# ProPrj___2024-08-30.net
KiCad netlist of a schematic drawn in EasyEDA Pro
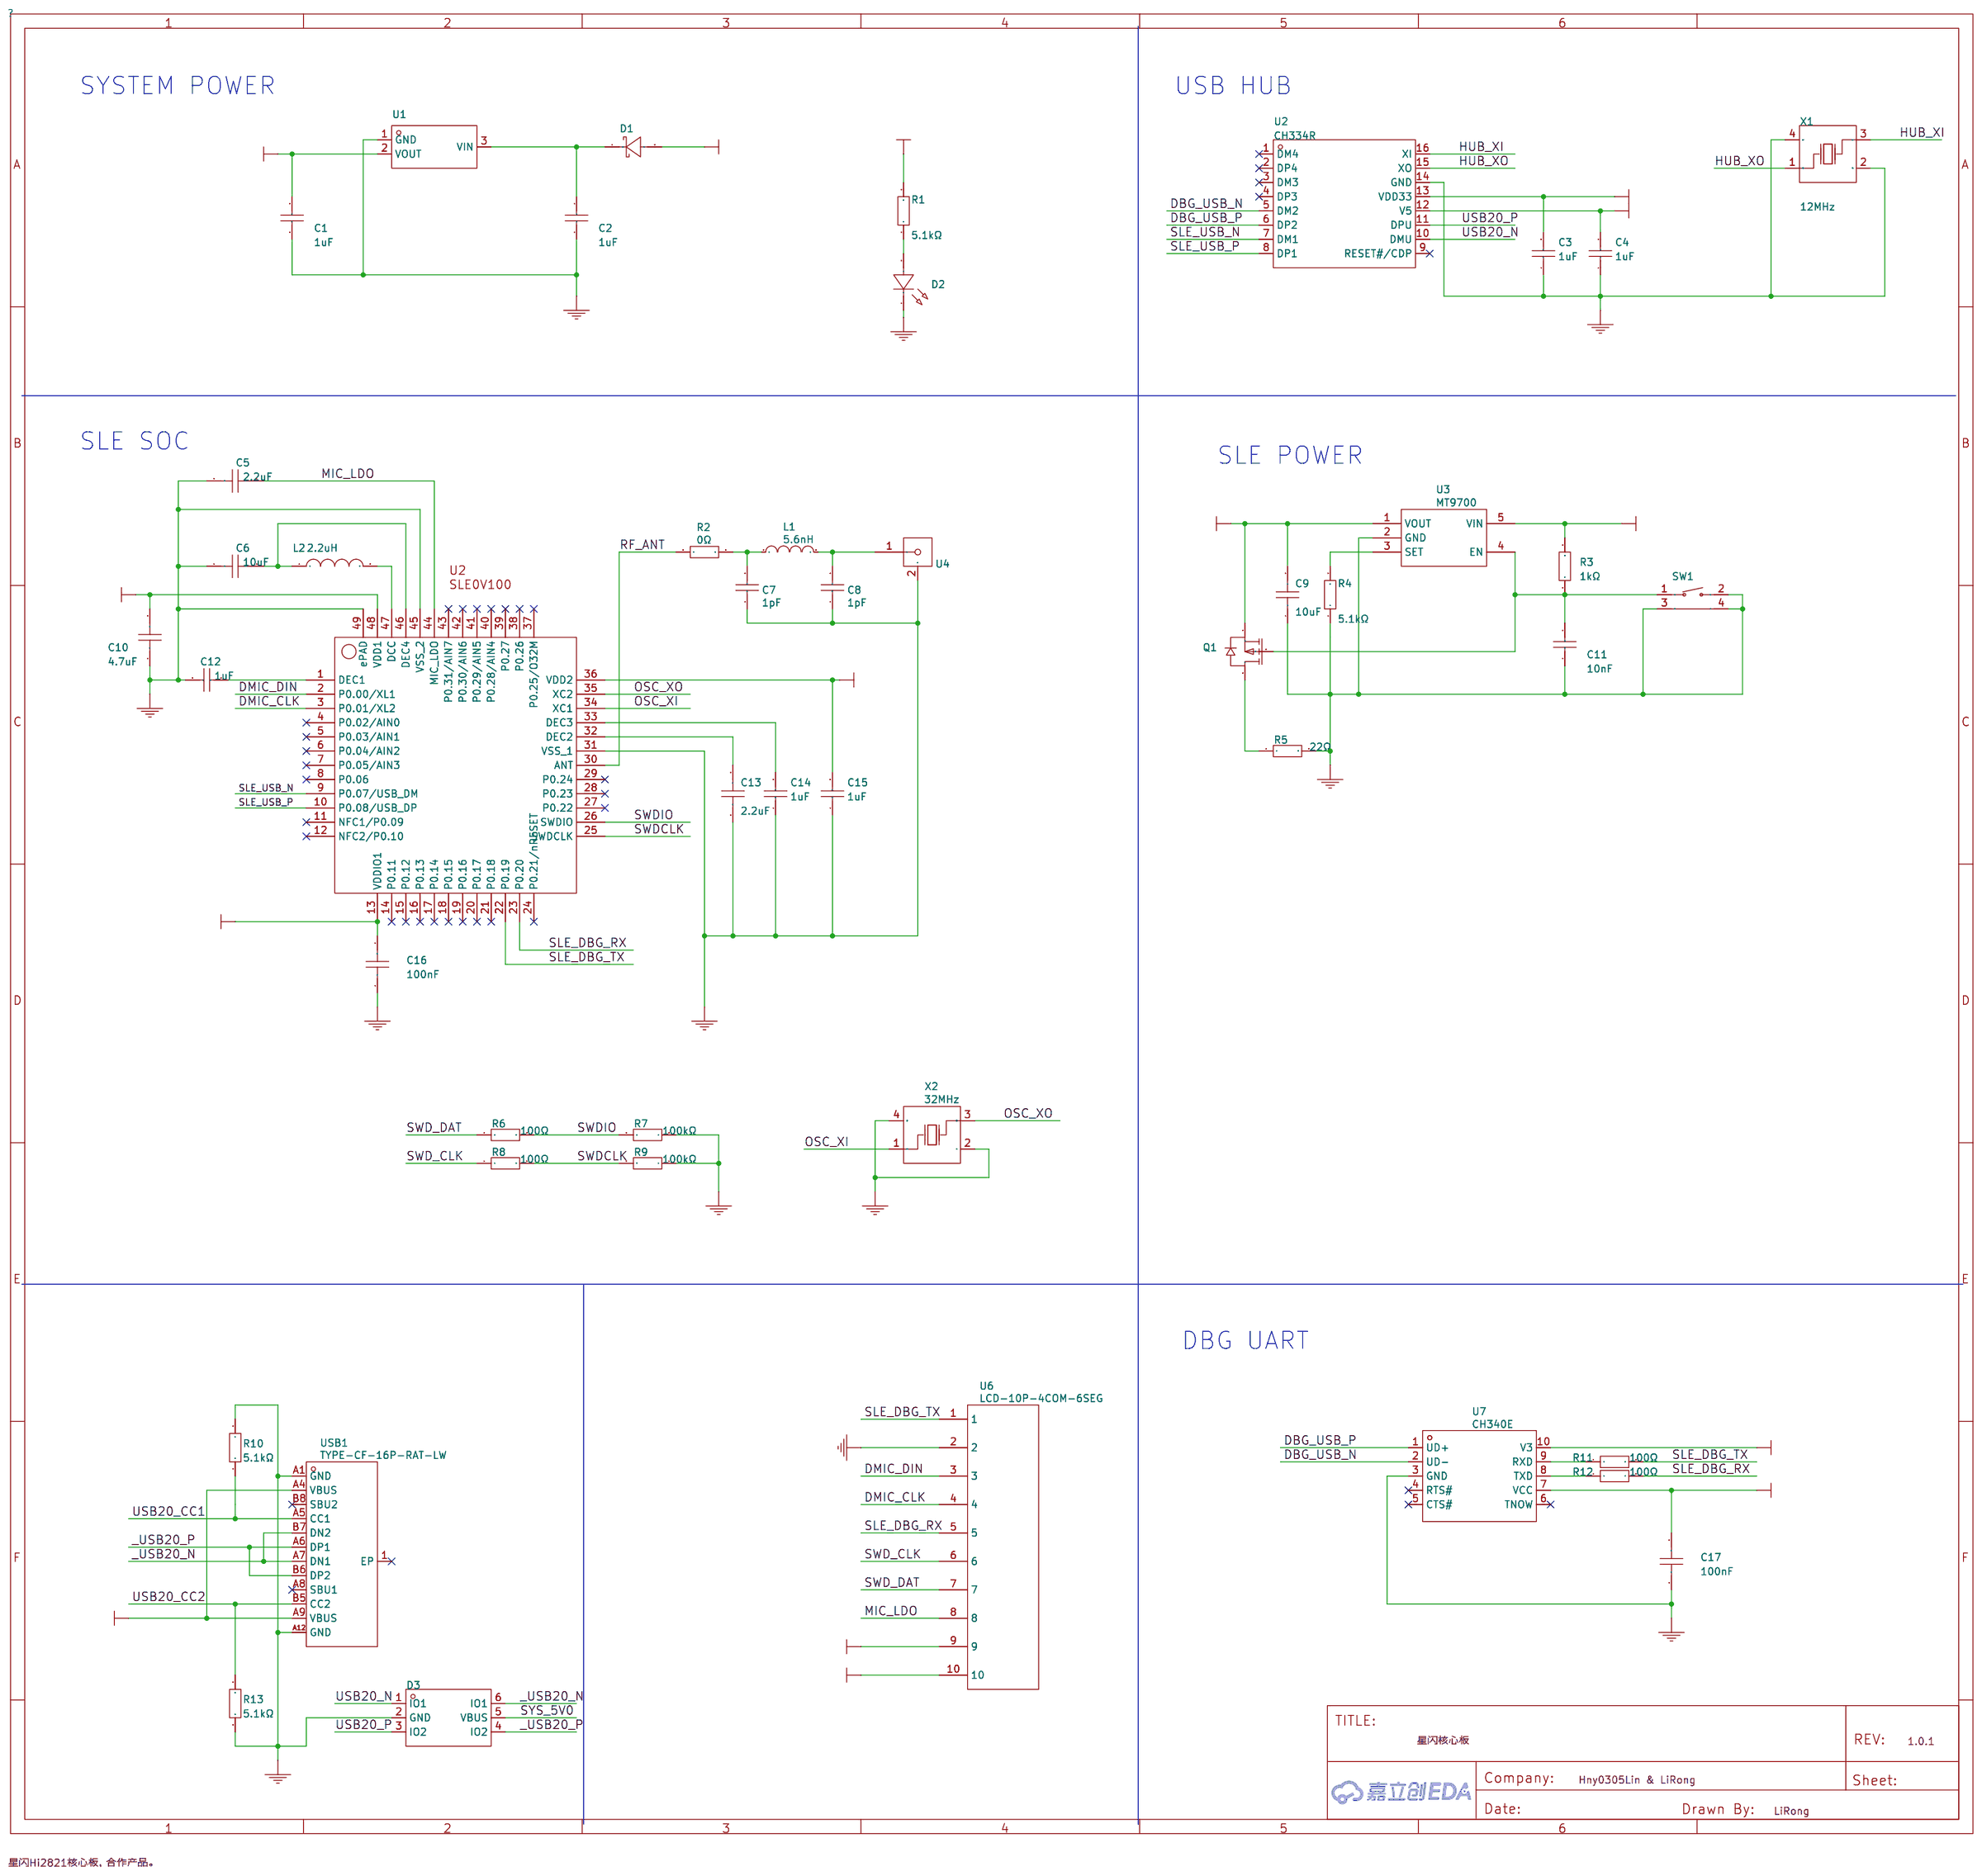
[diagram p0: schematic sheet]

(export (version "E")
  (design (tool "Eeschema 10.0.6"))
  (components
    (comp (ref "C1")
      (value "1uF")
      (footprint "easyedapro:C0603")
      (description "容值:1uF;精度:±10%;额定电压:16V;材质(温度系数):X5R;")
      (fields
        (field (name "Manufacturer Part") "CL10A105KO8NNNC")
        (field (name "Manufacturer") "SAMSUNG(三星)")
      )
      (libsource (lib "easyedapro") (part "CL10A105KO8NNNC"))
    )
    (comp (ref "C2")
      (value "1uF")
      (footprint "easyedapro:C0603")
      (description "容值:1uF;精度:±10%;额定电压:16V;材质(温度系数):X5R;")
      (fields
        (field (name "Manufacturer Part") "CL10A105KO8NNNC")
        (field (name "Manufacturer") "SAMSUNG(三星)")
      )
      (libsource (lib "easyedapro") (part "CL10A105KO8NNNC"))
    )
    (comp (ref "C3")
      (value "1uF")
      (footprint "easyedapro:C0402")
      (description "容值:1uF;精度:±10%;额定电压:10V;材质(温度系数):X5R;")
      (fields
        (field (name "Manufacturer Part") "CL05A105KP5NNNC")
        (field (name "Manufacturer") "SAMSUNG(三星)")
      )
      (libsource (lib "easyedapro") (part "CL05A105KP5NNNC"))
    )
    (comp (ref "C4")
      (value "1uF")
      (footprint "easyedapro:C0402")
      (description "容值:1uF;精度:±10%;额定电压:10V;材质(温度系数):X5R;")
      (fields
        (field (name "Manufacturer Part") "CL05A105KP5NNNC")
        (field (name "Manufacturer") "SAMSUNG(三星)")
      )
      (libsource (lib "easyedapro") (part "CL05A105KP5NNNC"))
    )
    (comp (ref "C5")
      (value "2.2uF")
      (footprint "easyedapro:C0402")
      (description "容值:2.2uF;精度:±10%;额定电压:10V;材质(温度系数):X5R;")
      (fields
        (field (name "Manufacturer Part") "CL05A225KP5NSNC")
        (field (name "Manufacturer") "SAMSUNG(三星)")
      )
      (libsource (lib "easyedapro") (part "CL05A225KP5NSNC"))
    )
    (comp (ref "C6")
      (value "10uF")
      (footprint "easyedapro:C0603")
      (description "容值:10uF;精度:±20%;额定电压:10V;材质(温度系数):X5R;")
      (fields
        (field (name "Manufacturer Part") "CL10A106MP8NNNC")
        (field (name "Manufacturer") "SAMSUNG(三星)")
      )
      (libsource (lib "easyedapro") (part "CL10A106MP8NNNC"))
    )
    (comp (ref "C7")
      (value "1pF")
      (footprint "easyedapro:C0201")
      (fields
        (field (name "Manufacturer Part") "GRM0335C1E1R0BA01D")
        (field (name "Manufacturer") "muRata(村田)")
      )
      (libsource (lib "easyedapro") (part "1pF"))
    )
    (comp (ref "C8")
      (value "1pF")
      (footprint "easyedapro:C0201")
      (fields
        (field (name "Manufacturer Part") "GRM0335C1E1R0BA01D")
        (field (name "Manufacturer") "muRata(村田)")
      )
      (libsource (lib "easyedapro") (part "1pF"))
    )
    (comp (ref "C9")
      (value "10uF")
      (footprint "easyedapro:C0603")
      (description "容值:10uF;精度:±20%;额定电压:10V;材质(温度系数):X5R;")
      (fields
        (field (name "Manufacturer Part") "CL10A106MP8NNNC")
        (field (name "Manufacturer") "SAMSUNG(三星)")
      )
      (libsource (lib "easyedapro") (part "CL10A106MP8NNNC"))
    )
    (comp (ref "C10")
      (value "4.7uF")
      (footprint "easyedapro:C0402")
      (description "容值:4.7uF;精度:±20%;额定电压:6.3V;材质(温度系数):X5R;")
      (fields
        (field (name "Manufacturer Part") "CL05A475MQ5NRNC")
        (field (name "Manufacturer") "SAMSUNG(三星)")
      )
      (libsource (lib "easyedapro") (part "CL05A475MQ5NRNC_C307423"))
    )
    (comp (ref "C11")
      (value "10nF")
      (footprint "easyedapro:C0402")
      (description "容值:10nF;精度:±10%;额定电压:50V;材质(温度系数):X7R;")
      (fields
        (field (name "Manufacturer Part") "CC0402KRX7R9BB103")
        (field (name "Manufacturer") "YAGEO(国巨)")
      )
      (libsource (lib "easyedapro") (part "CC0402KRX7R9BB103"))
    )
    (comp (ref "C12")
      (value "1uF")
      (footprint "easyedapro:C0402")
      (description "容值:1uF;精度:±10%;额定电压:10V;材质(温度系数):X5R;")
      (fields
        (field (name "Manufacturer Part") "CL05A105KP5NNNC")
        (field (name "Manufacturer") "SAMSUNG(三星)")
      )
      (libsource (lib "easyedapro") (part "CL05A105KP5NNNC"))
    )
    (comp (ref "C13")
      (value "2.2uF")
      (footprint "easyedapro:C0402")
      (description "容值:2.2uF;精度:±10%;额定电压:10V;材质(温度系数):X5R;")
      (fields
        (field (name "Manufacturer Part") "CL05A225KP5NSNC")
        (field (name "Manufacturer") "SAMSUNG(三星)")
      )
      (libsource (lib "easyedapro") (part "CL05A225KP5NSNC"))
    )
    (comp (ref "C14")
      (value "1uF")
      (footprint "easyedapro:C0402")
      (description "容值:1uF;精度:±10%;额定电压:10V;材质(温度系数):X5R;")
      (fields
        (field (name "Manufacturer Part") "CL05A105KP5NNNC")
        (field (name "Manufacturer") "SAMSUNG(三星)")
      )
      (libsource (lib "easyedapro") (part "CL05A105KP5NNNC"))
    )
    (comp (ref "C15")
      (value "1uF")
      (footprint "easyedapro:C0402")
      (description "容值:1uF;精度:±10%;额定电压:10V;材质(温度系数):X5R;")
      (fields
        (field (name "Manufacturer Part") "CL05A105KP5NNNC")
        (field (name "Manufacturer") "SAMSUNG(三星)")
      )
      (libsource (lib "easyedapro") (part "CL05A105KP5NNNC"))
    )
    (comp (ref "C16")
      (value "100nF")
      (footprint "easyedapro:C0402")
      (description "容值:100nF;精度:±10%;额定电压:16V;材质(温度系数):X7R;")
      (fields
        (field (name "Manufacturer Part") "CL05B104KO5NNNC")
        (field (name "Manufacturer") "SAMSUNG(三星)")
      )
      (libsource (lib "easyedapro") (part "CL05B104KO5NNNC"))
    )
    (comp (ref "C17")
      (value "100nF")
      (footprint "easyedapro:C0402")
      (description "容值:100nF;精度:±10%;额定电压:16V;材质(温度系数):X7R;")
      (fields
        (field (name "Manufacturer Part") "CL05B104KO5NNNC")
        (field (name "Manufacturer") "SAMSUNG(三星)")
      )
      (libsource (lib "easyedapro") (part "CL05B104KO5NNNC"))
    )
    (comp (ref "D1")
      (value "B5817WS")
      (footprint "easyedapro:SOD-323_L1.7-W1.3-LS2.5-RD")
      (description "二极管配置:独立式;正向压降(Vf):450mV@1A;直流反向耐压(Vr):20V;平均整流电流(Io):1A;")
      (fields (field (name "Manufacturer") "FUXINSEMI(富芯森美)"))
      (libsource (lib "easyedapro") (part "B5817WS_C5178966"))
    )
    (comp (ref "D2")
      (value "XL-1608SURC-06")
      (footprint "easyedapro:LED0603-RD_RED")
      (fields (field (name "Manufacturer Part") "红色LED"))
      (libsource (lib "easyedapro") (part "红色LED"))
    )
    (comp (ref "D3")
      (value "USBLC6-2SC6")
      (footprint "easyedapro:SOT-23-6_L2.9-W1.6-P0.95-LS2.8-BL")
      (description "极性:-;反向截止电压(Vrwm):-;最大钳位电压:-;峰值脉冲电流(Ipp)@10/1000us:-;峰值脉冲功率(Ppp)@10/1000us:-;击穿电压:-;")
      (fields (field (name "Manufacturer") "TECH PUBLIC(台舟)"))
      (libsource (lib "easyedapro") (part "USBLC6-2SC6_C2827654"))
    )
    (comp (ref "L1")
      (value "5.6nH")
      (footprint "easyedapro:L0201")
      (fields (field (name "Manufacturer Part") "LQP03TN5N6H02D") (field (name "Manufacturer") "muRata(村田)"))
      (libsource (lib "easyedapro") (part "5.6nH"))
    )
    (comp (ref "L2")
      (value "2.2uH")
      (footprint "easyedapro:0805")
      (fields (field (name "Manufacturer") "microgate(麦捷科技)"))
      (libsource (lib "easyedapro") (part "INDUCTOR0805"))
    )
    (comp (ref "Q1")
      (value "RU20P7C-A")
      (footprint "easyedapro:SOT-23-3_L3.0-W1.6-P1.90-LS2.8-BR")
      (fields (field (name "Manufacturer") "Ruichips(锐骏半导体)"))
      (libsource (lib "easyedapro") (part "RU20P7C-A"))
    )
    (comp (ref "R1")
      (value "5.1kΩ")
      (footprint "easyedapro:R0402")
      (description "电阻类型:厚膜电阻;阻值:5.1kΩ;精度:±1%;功率:62.5mW;最大工作电压:50V;温度系数:±100ppm/°C;")
      (fields
        (field (name "Manufacturer Part") "0402WGF5101TCE")
        (field (name "Manufacturer") "UNI-ROYAL(厚声)")
      )
      (libsource (lib "easyedapro") (part "0402WGF5101TCE"))
    )
    (comp (ref "R2")
      (value "0Ω")
      (footprint "easyedapro:R0201")
      (fields
        (field (name "Manufacturer Part") "0201WMJ0000TEE")
        (field (name "Manufacturer") "UNI-ROYAL(厚声)")
      )
      (libsource (lib "easyedapro") (part "0Ω"))
    )
    (comp (ref "R3")
      (value "1kΩ")
      (footprint "easyedapro:R0402")
      (description "电阻类型:厚膜电阻;阻值:1kΩ;精度:±1%;功率:62.5mW;最大工作电压:50V;温度系数:±100ppm/°C;")
      (fields
        (field (name "Manufacturer Part") "0402WGF1001TCE")
        (field (name "Manufacturer") "UNI-ROYAL(厚声)")
      )
      (libsource (lib "easyedapro") (part "0402WGF1001TCE"))
    )
    (comp (ref "R4")
      (value "5.1kΩ")
      (footprint "easyedapro:R0402")
      (description "电阻类型:厚膜电阻;阻值:5.1kΩ;精度:±1%;功率:62.5mW;最大工作电压:50V;温度系数:±100ppm/°C;")
      (fields
        (field (name "Manufacturer Part") "0402WGF5101TCE")
        (field (name "Manufacturer") "UNI-ROYAL(厚声)")
      )
      (libsource (lib "easyedapro") (part "0402WGF5101TCE"))
    )
    (comp (ref "R5")
      (value "22Ω")
      (footprint "easyedapro:R0402")
      (description "电阻类型:厚膜电阻;阻值:22Ω;精度:±1%;功率:62.5mW;最大工作电压:50V;温度系数:±100ppm/°C;")
      (fields
        (field (name "Manufacturer Part") "0402WGF220JTCE")
        (field (name "Manufacturer") "UNI-ROYAL(厚声)")
      )
      (libsource (lib "easyedapro") (part "0402WGF220JTCE"))
    )
    (comp (ref "R6")
      (value "100Ω")
      (footprint "easyedapro:R0402")
      (description "电阻类型:厚膜电阻;阻值:100Ω;精度:±1%;功率:62.5mW;最大工作电压:50V;温度系数:±200ppm/°C;")
      (fields
        (field (name "Manufacturer Part") "0402WGF1000TCE")
        (field (name "Manufacturer") "UNI-ROYAL(厚声)")
      )
      (libsource (lib "easyedapro") (part "0402WGF1000TCE"))
    )
    (comp (ref "R7")
      (value "100kΩ")
      (footprint "easyedapro:R0402")
      (description "电阻类型:厚膜电阻;阻值:100kΩ;精度:±1%;功率:62.5mW;最大工作电压:50V;温度系数:±100ppm/°C;")
      (fields (field (name "Manufacturer Part") "RC0402FR-07100KL") (field (name "Manufacturer") "YAGEO(国巨)"))
      (libsource (lib "easyedapro") (part "RC0402FR-07100KL"))
    )
    (comp (ref "R8")
      (value "100Ω")
      (footprint "easyedapro:R0402")
      (description "电阻类型:厚膜电阻;阻值:100Ω;精度:±1%;功率:62.5mW;最大工作电压:50V;温度系数:±200ppm/°C;")
      (fields
        (field (name "Manufacturer Part") "0402WGF1000TCE")
        (field (name "Manufacturer") "UNI-ROYAL(厚声)")
      )
      (libsource (lib "easyedapro") (part "0402WGF1000TCE"))
    )
    (comp (ref "R9")
      (value "100kΩ")
      (footprint "easyedapro:R0402")
      (description "电阻类型:厚膜电阻;阻值:100kΩ;精度:±1%;功率:62.5mW;最大工作电压:50V;温度系数:±100ppm/°C;")
      (fields (field (name "Manufacturer Part") "RC0402FR-07100KL") (field (name "Manufacturer") "YAGEO(国巨)"))
      (libsource (lib "easyedapro") (part "RC0402FR-07100KL"))
    )
    (comp (ref "R10")
      (value "5.1kΩ")
      (footprint "easyedapro:R0402")
      (description "电阻类型:厚膜电阻;阻值:5.1kΩ;精度:±1%;功率:62.5mW;最大工作电压:50V;温度系数:±100ppm/°C;")
      (fields
        (field (name "Manufacturer Part") "0402WGF5101TCE")
        (field (name "Manufacturer") "UNI-ROYAL(厚声)")
      )
      (libsource (lib "easyedapro") (part "0402WGF5101TCE"))
    )
    (comp (ref "R11")
      (value "100Ω")
      (footprint "easyedapro:R0402")
      (description "电阻类型:厚膜电阻;阻值:100Ω;精度:±1%;功率:62.5mW;最大工作电压:50V;温度系数:±200ppm/°C;")
      (fields
        (field (name "Manufacturer Part") "0402WGF1000TCE")
        (field (name "Manufacturer") "UNI-ROYAL(厚声)")
      )
      (libsource (lib "easyedapro") (part "0402WGF1000TCE"))
    )
    (comp (ref "R12")
      (value "100Ω")
      (footprint "easyedapro:R0402")
      (description "电阻类型:厚膜电阻;阻值:100Ω;精度:±1%;功率:62.5mW;最大工作电压:50V;温度系数:±200ppm/°C;")
      (fields
        (field (name "Manufacturer Part") "0402WGF1000TCE")
        (field (name "Manufacturer") "UNI-ROYAL(厚声)")
      )
      (libsource (lib "easyedapro") (part "0402WGF1000TCE"))
    )
    (comp (ref "R13")
      (value "5.1kΩ")
      (footprint "easyedapro:R0402")
      (description "电阻类型:厚膜电阻;阻值:5.1kΩ;精度:±1%;功率:62.5mW;最大工作电压:50V;温度系数:±100ppm/°C;")
      (fields
        (field (name "Manufacturer Part") "0402WGF5101TCE")
        (field (name "Manufacturer") "UNI-ROYAL(厚声)")
      )
      (libsource (lib "easyedapro") (part "0402WGF5101TCE"))
    )
    (comp (ref "SW1")
      (value "TS-1135-C")
      (footprint "easyedapro:SW-SMD_YIYUAN_YTS-B017-2H")
      (fields (field (name "Manufacturer") "XKB Connectivity(中国星坤)"))
      (libsource (lib "easyedapro") (part "TS-1135-C"))
    )
    (comp (ref "U1")
      (value "XC6206-3.3NR")
      (footprint "easyedapro:SOT-23-3_L2.9-W1.3-P0.95-LS2.4-BR")
      (fields (field (name "Manufacturer") "HX(恒佳兴)"))
      (libsource (lib "easyedapro") (part "XC6206-3.3NR"))
    )
    (comp (ref "U2")
      (value "CH334R")
      (footprint "easyedapro:QSOP-16_L4.9-W3.9-P0.64-LS6.0-BL")
      (fields (field (name "Manufacturer") "WCH(南京沁恒)"))
      (libsource (lib "easyedapro") (part "CH334R"))
    )
    (comp (ref "U3")
      (value "MT9700")
      (footprint "easyedapro:SOT-23-5_L3.0-W1.7-P0.95-LS2.8-BR")
      (fields (field (name "Manufacturer") "西安航天民芯"))
      (libsource (lib "easyedapro") (part "MT9700"))
    )
    (comp (ref "U4")
      (value "U.FL-R-SMT-1(80)_C9900020048")
      (footprint "easyedapro:IPEX-SMD_4P-L2.6-W2.6-LS3.0-1")
      (fields (field (name "Manufacturer Part") "U.FL-R-SMT-1(80)"))
      (libsource (lib "easyedapro") (part "U.FL-R-SMT-1(80)_C9900020048"))
    )
    (comp (ref "U5")
      (value "SLE0V100(1)")
      (footprint "easyedapro:QFN_48XINGSHAN")
      (libsource (lib "easyedapro") (part "SLE0V100(1)"))
    )
    (comp (ref "U6")
      (value "LCD-10P-4COM-6SEG")
      (footprint "easyedapro:DU10_3.5")
      (libsource (lib "easyedapro") (part "LCD-10P-4COM-6SEG"))
    )
    (comp (ref "U7")
      (value "CH340E")
      (footprint "easyedapro:MSOP-10_L3.0-W3.0-P0.50-LS5.0-BL")
      (fields (field (name "Manufacturer") "WCH(南京沁恒)"))
      (libsource (lib "easyedapro") (part "CH340E"))
    )
    (comp (ref "USB1")
      (value "TYPE-CF-16P-RAT-LW")
      (footprint "easyedapro:TYPE-C-SMD_TYPE-CF-16P-RAT-LW")
      (libsource (lib "easyedapro") (part "TYPE-CF-16P-RAT-LW"))
    )
    (comp (ref "X1")
      (value "12MHz")
      (footprint "easyedapro:OSC-SMD_4P-L3.2-W2.5-BL")
      (description "晶振类型:贴片晶振;频率:12MHz;常温频差:±10ppm;外接负载电容:20pF;频率稳定度(全温):±20ppm;")
      (fields (field (name "Manufacturer Part") "X322512MSB4SI") (field (name "Manufacturer") "YXC(扬兴晶振)"))
      (libsource (lib "easyedapro") (part "X322512MSB4SI"))
    )
    (comp (ref "X2")
      (value "32MHz")
      (footprint "easyedapro:CRYSTAL-SMD_4P-L3.2-W2.5-BL")
      (fields (field (name "Manufacturer Part") "X322532MOB4SI") (field (name "Manufacturer") "YXC(扬兴晶振)"))
      (libsource (lib "easyedapro") (part "32MHz"))
    )
  )
  (nets
    (net (code "1") (name "/DBG_USB_N") (class "Default")
      (node (ref "U2") (pin "5") (pinfunction "DM2_5") (pintype "unspecified"))
      (node (ref "U7") (pin "2") (pinfunction "UD-_2") (pintype "unspecified"))
    )
    (net (code "2") (name "/DBG_USB_P") (class "Default")
      (node (ref "U2") (pin "6") (pinfunction "DP2_6") (pintype "unspecified"))
      (node (ref "U7") (pin "1") (pinfunction "UD+_1") (pintype "unspecified"))
    )
    (net (code "3") (name "/DMIC_CLK") (class "Default")
      (node (ref "U5") (pin "3") (pinfunction "P0.01/XL2_3") (pintype "unspecified"))
      (node (ref "U6") (pin "4") (pinfunction "4_4") (pintype "unspecified"))
    )
    (net (code "4") (name "/DMIC_DIN") (class "Default")
      (node (ref "U5") (pin "2") (pinfunction "P0.00/XL1_2") (pintype "unspecified"))
      (node (ref "U6") (pin "3") (pinfunction "3_3") (pintype "unspecified"))
    )
    (net (code "5") (name "/HUB_XI") (class "Default")
      (node (ref "U2") (pin "16") (pinfunction "XI_16") (pintype "unspecified"))
      (node (ref "X1") (pin "3") (pinfunction "OSC2_3") (pintype "unspecified"))
    )
    (net (code "6") (name "/HUB_XO") (class "Default")
      (node (ref "U2") (pin "15") (pinfunction "XO_15") (pintype "unspecified"))
      (node (ref "X1") (pin "1") (pinfunction "OSC1_1") (pintype "unspecified"))
    )
    (net (code "7") (name "/MIC_LDO") (class "Default")
      (node (ref "C5") (pin "1") (pinfunction "1_1") (pintype "unspecified"))
      (node (ref "U5") (pin "44") (pinfunction "MIC_LDO_44") (pintype "unspecified"))
      (node (ref "U6") (pin "8") (pinfunction "8_8") (pintype "unspecified"))
    )
    (net (code "8") (name "/OSC_XI") (class "Default")
      (node (ref "U5") (pin "34") (pinfunction "XC1_34") (pintype "unspecified"))
      (node (ref "X2") (pin "1") (pinfunction "OSC1_1") (pintype "unspecified"))
    )
    (net (code "9") (name "/OSC_XO") (class "Default")
      (node (ref "U5") (pin "35") (pinfunction "XC2_35") (pintype "unspecified"))
      (node (ref "X2") (pin "3") (pinfunction "OSC2_3") (pintype "unspecified"))
    )
    (net (code "10") (name "/RF_ANT") (class "Default")
      (node (ref "R2") (pin "1") (pinfunction "1_1") (pintype "unspecified"))
      (node (ref "U5") (pin "30") (pinfunction "ANT_30") (pintype "unspecified"))
    )
    (net (code "11") (name "/SLE_DBG_RX") (class "Default")
      (node (ref "R12") (pin "2") (pinfunction "2_2") (pintype "input"))
      (node (ref "U5") (pin "23") (pinfunction "P0.20_23") (pintype "unspecified"))
      (node (ref "U6") (pin "5") (pinfunction "5_5") (pintype "unspecified"))
    )
    (net (code "12") (name "/SLE_DBG_TX") (class "Default")
      (node (ref "R11") (pin "2") (pinfunction "2_2") (pintype "input"))
      (node (ref "U5") (pin "22") (pinfunction "P0.19_22") (pintype "unspecified"))
      (node (ref "U6") (pin "1") (pinfunction "1_1") (pintype "unspecified"))
    )
    (net (code "13") (name "/SLE_USB_N") (class "Default")
      (node (ref "U2") (pin "7") (pinfunction "DM1_7") (pintype "unspecified"))
      (node (ref "U5") (pin "9") (pinfunction "P0.07/USB_DM_9") (pintype "unspecified"))
    )
    (net (code "14") (name "/SLE_USB_P") (class "Default")
      (node (ref "U2") (pin "8") (pinfunction "DP1_8") (pintype "unspecified"))
      (node (ref "U5") (pin "10") (pinfunction "P0.08/USB_DP_10") (pintype "unspecified"))
    )
    (net (code "15") (name "/SWDCLK") (class "Default")
      (node (ref "R8") (pin "2") (pinfunction "2_2") (pintype "input"))
      (node (ref "R9") (pin "2") (pinfunction "2_2") (pintype "input"))
      (node (ref "U5") (pin "25") (pinfunction "SWDCLK_25") (pintype "unspecified"))
    )
    (net (code "16") (name "/SWDIO") (class "Default")
      (node (ref "R6") (pin "2") (pinfunction "2_2") (pintype "input"))
      (node (ref "R7") (pin "2") (pinfunction "2_2") (pintype "input"))
      (node (ref "U5") (pin "26") (pinfunction "SWDIO_26") (pintype "unspecified"))
    )
    (net (code "17") (name "/SWD_CLK") (class "Default")
      (node (ref "R8") (pin "1") (pinfunction "1_1") (pintype "input"))
      (node (ref "U6") (pin "6") (pinfunction "6_6") (pintype "unspecified"))
    )
    (net (code "18") (name "/SWD_DAT") (class "Default")
      (node (ref "R6") (pin "1") (pinfunction "1_1") (pintype "input"))
      (node (ref "U6") (pin "7") (pinfunction "7_7") (pintype "unspecified"))
    )
    (net (code "19") (name "/USB20_CC1") (class "Default")
      (node (ref "R10") (pin "1") (pinfunction "1_1") (pintype "input"))
      (node (ref "USB1") (pin "A5") (pinfunction "CC1_A5") (pintype "unspecified"))
    )
    (net (code "20") (name "/USB20_CC2") (class "Default")
      (node (ref "R13") (pin "2") (pinfunction "2_2") (pintype "input"))
      (node (ref "USB1") (pin "B5") (pinfunction "CC2_B5") (pintype "unspecified"))
    )
    (net (code "21") (name "/USB20_N") (class "Default")
      (node (ref "D3") (pin "1") (pinfunction "IO1_1") (pintype "unspecified"))
      (node (ref "U2") (pin "10") (pinfunction "DMU_10") (pintype "unspecified"))
    )
    (net (code "22") (name "/USB20_P") (class "Default")
      (node (ref "D3") (pin "3") (pinfunction "IO2_3") (pintype "unspecified"))
      (node (ref "U2") (pin "11") (pinfunction "DPU_11") (pintype "unspecified"))
    )
    (net (code "23") (name "/_USB20_N") (class "Default")
      (node (ref "D3") (pin "6") (pinfunction "IO1_6") (pintype "unspecified"))
      (node (ref "USB1") (pin "A7") (pinfunction "DN1_A7") (pintype "unspecified"))
      (node (ref "USB1") (pin "B7") (pinfunction "DN2_B7") (pintype "unspecified"))
    )
    (net (code "24") (name "/_USB20_P") (class "Default")
      (node (ref "D3") (pin "4") (pinfunction "IO2_4") (pintype "unspecified"))
      (node (ref "USB1") (pin "A6") (pinfunction "DP1_A6") (pintype "unspecified"))
      (node (ref "USB1") (pin "B6") (pinfunction "DP2_B6") (pintype "unspecified"))
    )
    (net (code "25") (name "DBG_3V3") (class "Default")
      (node (ref "C17") (pin "2") (pinfunction "2_2") (pintype "unspecified"))
      (node (ref "C3") (pin "2") (pinfunction "2_2") (pintype "input"))
      (node (ref "U2") (pin "13") (pinfunction "VDD33_13") (pintype "unspecified"))
      (node (ref "U7") (pin "10") (pinfunction "V3_10") (pintype "unspecified"))
      (node (ref "U7") (pin "7") (pinfunction "VCC_7") (pintype "unspecified"))
    )
    (net (code "26") (name "GND") (class "Default")
      (node (ref "C1") (pin "1") (pinfunction "1_1") (pintype "input"))
      (node (ref "C10") (pin "1") (pinfunction "1_1") (pintype "unspecified"))
      (node (ref "C11") (pin "1") (pinfunction "1_1") (pintype "input"))
      (node (ref "C12") (pin "1") (pinfunction "1_1") (pintype "input"))
      (node (ref "C13") (pin "1") (pinfunction "1_1") (pintype "unspecified"))
      (node (ref "C14") (pin "1") (pinfunction "1_1") (pintype "input"))
      (node (ref "C15") (pin "1") (pinfunction "1_1") (pintype "input"))
      (node (ref "C16") (pin "1") (pinfunction "1_1") (pintype "unspecified"))
      (node (ref "C17") (pin "1") (pinfunction "1_1") (pintype "unspecified"))
      (node (ref "C2") (pin "1") (pinfunction "1_1") (pintype "input"))
      (node (ref "C3") (pin "1") (pinfunction "1_1") (pintype "input"))
      (node (ref "C4") (pin "1") (pinfunction "1_1") (pintype "input"))
      (node (ref "C5") (pin "2") (pinfunction "2_2") (pintype "unspecified"))
      (node (ref "C6") (pin "1") (pinfunction "1_1") (pintype "unspecified"))
      (node (ref "C7") (pin "1") (pinfunction "1_1") (pintype "input"))
      (node (ref "C8") (pin "1") (pinfunction "1_1") (pintype "input"))
      (node (ref "C9") (pin "1") (pinfunction "1_1") (pintype "unspecified"))
      (node (ref "D2") (pin "1") (pinfunction "K_1") (pintype "unspecified"))
      (node (ref "D3") (pin "2") (pinfunction "GND_2") (pintype "unspecified"))
      (node (ref "R10") (pin "2") (pinfunction "2_2") (pintype "input"))
      (node (ref "R13") (pin "1") (pinfunction "1_1") (pintype "input"))
      (node (ref "R4") (pin "1") (pinfunction "1_1") (pintype "input"))
      (node (ref "R5") (pin "2") (pinfunction "2_2") (pintype "input"))
      (node (ref "R7") (pin "1") (pinfunction "1_1") (pintype "input"))
      (node (ref "R9") (pin "1") (pinfunction "1_1") (pintype "input"))
      (node (ref "SW1") (pin "2") (pinfunction "2_2") (pintype "input"))
      (node (ref "SW1") (pin "3") (pinfunction "3_3") (pintype "input"))
      (node (ref "SW1") (pin "4") (pinfunction "4_4") (pintype "input"))
      (node (ref "U1") (pin "1") (pinfunction "GND_1") (pintype "unspecified"))
      (node (ref "U2") (pin "14") (pinfunction "GND_14") (pintype "unspecified"))
      (node (ref "U3") (pin "2") (pinfunction "GND_2") (pintype "unspecified"))
      (node (ref "U4") (pin "2") (pinfunction "2_2") (pintype "unspecified"))
      (node (ref "U5") (pin "31") (pinfunction "VSS_1_31") (pintype "unspecified"))
      (node (ref "U5") (pin "45") (pinfunction "VSS_2_45") (pintype "unspecified"))
      (node (ref "U5") (pin "49") (pinfunction "ePAD_49") (pintype "unspecified"))
      (node (ref "U6") (pin "2") (pinfunction "2_2") (pintype "unspecified"))
      (node (ref "U7") (pin "3") (pinfunction "GND_3") (pintype "unspecified"))
      (node (ref "USB1") (pin "A1") (pinfunction "GND_A1") (pintype "unspecified"))
      (node (ref "USB1") (pin "A12") (pinfunction "GND_A12") (pintype "unspecified"))
      (node (ref "X1") (pin "2") (pinfunction "GND_2") (pintype "unspecified"))
      (node (ref "X1") (pin "4") (pinfunction "GND_4") (pintype "unspecified"))
      (node (ref "X2") (pin "2") (pinfunction "GND_2") (pintype "unspecified"))
      (node (ref "X2") (pin "4") (pinfunction "GND_4") (pintype "unspecified"))
    )
    (net (code "27") (name "Net-(C7-Pad2)") (class "Default")
      (node (ref "C7") (pin "2") (pinfunction "2_2") (pintype "input"))
      (node (ref "L1") (pin "1") (pinfunction "1_1") (pintype "unspecified"))
      (node (ref "R2") (pin "2") (pinfunction "2_2") (pintype "unspecified"))
    )
    (net (code "28") (name "Net-(C8-Pad2)") (class "Default")
      (node (ref "C8") (pin "2") (pinfunction "2_2") (pintype "input"))
      (node (ref "L1") (pin "2") (pinfunction "2_2") (pintype "unspecified"))
      (node (ref "U4") (pin "1") (pinfunction "1_1") (pintype "unspecified"))
    )
    (net (code "29") (name "Net-(D1-C)") (class "Default")
      (node (ref "C2") (pin "2") (pinfunction "2_2") (pintype "input"))
      (node (ref "D1") (pin "1") (pinfunction "C_1") (pintype "unspecified"))
      (node (ref "U1") (pin "3") (pinfunction "VIN_3") (pintype "unspecified"))
    )
    (net (code "30") (name "Net-(D2-A)") (class "Default")
      (node (ref "D2") (pin "2") (pinfunction "A_2") (pintype "unspecified"))
      (node (ref "R1") (pin "1") (pinfunction "1_1") (pintype "input"))
    )
    (net (code "31") (name "Net-(Q1-D)") (class "Default")
      (node (ref "Q1") (pin "3") (pinfunction "D_3") (pintype "unspecified"))
      (node (ref "R5") (pin "1") (pinfunction "1_1") (pintype "input"))
    )
    (net (code "32") (name "Net-(Q1-G)") (class "Default")
      (node (ref "C11") (pin "2") (pinfunction "2_2") (pintype "input"))
      (node (ref "Q1") (pin "1") (pinfunction "G_1") (pintype "unspecified"))
      (node (ref "R3") (pin "1") (pinfunction "1_1") (pintype "input"))
      (node (ref "SW1") (pin "1") (pinfunction "1_1") (pintype "input"))
      (node (ref "U3") (pin "4") (pinfunction "EN_4") (pintype "unspecified"))
    )
    (net (code "33") (name "Net-(U3-SET)") (class "Default")
      (node (ref "R4") (pin "2") (pinfunction "2_2") (pintype "input"))
      (node (ref "U3") (pin "3") (pinfunction "SET_3") (pintype "unspecified"))
    )
    (net (code "34") (name "Net-(U5-DCC)") (class "Default")
      (node (ref "L2") (pin "2") (pinfunction "2_2") (pintype "unspecified"))
      (node (ref "U5") (pin "47") (pinfunction "DCC_47") (pintype "unspecified"))
    )
    (net (code "35") (name "Net-(U5-DEC1)") (class "Default")
      (node (ref "C12") (pin "2") (pinfunction "2_2") (pintype "input"))
      (node (ref "U5") (pin "1") (pinfunction "DEC1_1") (pintype "unspecified"))
    )
    (net (code "36") (name "Net-(U5-DEC2)") (class "Default")
      (node (ref "C13") (pin "2") (pinfunction "2_2") (pintype "unspecified"))
      (node (ref "U5") (pin "32") (pinfunction "DEC2_32") (pintype "unspecified"))
    )
    (net (code "37") (name "Net-(U5-DEC3)") (class "Default")
      (node (ref "C14") (pin "2") (pinfunction "2_2") (pintype "input"))
      (node (ref "U5") (pin "33") (pinfunction "DEC3_33") (pintype "unspecified"))
    )
    (net (code "38") (name "Net-(U5-DEC4)") (class "Default")
      (node (ref "C6") (pin "2") (pinfunction "2_2") (pintype "unspecified"))
      (node (ref "L2") (pin "1") (pinfunction "1_1") (pintype "unspecified"))
      (node (ref "U5") (pin "46") (pinfunction "DEC4_46") (pintype "unspecified"))
    )
    (net (code "39") (name "Net-(U7-RXD)") (class "Default")
      (node (ref "R11") (pin "1") (pinfunction "1_1") (pintype "input"))
      (node (ref "U7") (pin "9") (pinfunction "RXD_9") (pintype "unspecified"))
    )
    (net (code "40") (name "Net-(U7-TXD)") (class "Default")
      (node (ref "R12") (pin "1") (pinfunction "1_1") (pintype "input"))
      (node (ref "U7") (pin "8") (pinfunction "TXD_8") (pintype "unspecified"))
    )
    (net (code "41") (name "SLE_3V3") (class "Default")
      (node (ref "C10") (pin "2") (pinfunction "2_2") (pintype "unspecified"))
      (node (ref "C15") (pin "2") (pinfunction "2_2") (pintype "input"))
      (node (ref "C16") (pin "2") (pinfunction "2_2") (pintype "unspecified"))
      (node (ref "C9") (pin "2") (pinfunction "2_2") (pintype "unspecified"))
      (node (ref "Q1") (pin "2") (pinfunction "S_2") (pintype "unspecified"))
      (node (ref "U3") (pin "1") (pinfunction "VOUT_1") (pintype "unspecified"))
      (node (ref "U5") (pin "13") (pinfunction "VDDIO1_13") (pintype "unspecified"))
      (node (ref "U5") (pin "36") (pinfunction "VDD2_36") (pintype "unspecified"))
      (node (ref "U5") (pin "48") (pinfunction "VDD1_48") (pintype "unspecified"))
    )
    (net (code "42") (name "SYS_3V3") (class "Default")
      (node (ref "C1") (pin "2") (pinfunction "2_2") (pintype "input"))
      (node (ref "R1") (pin "2") (pinfunction "2_2") (pintype "input"))
      (node (ref "R3") (pin "2") (pinfunction "2_2") (pintype "input"))
      (node (ref "U1") (pin "2") (pinfunction "VOUT_2") (pintype "unspecified"))
      (node (ref "U3") (pin "5") (pinfunction "VIN_5") (pintype "unspecified"))
      (node (ref "U6") (pin "9") (pinfunction "9_9") (pintype "unspecified"))
    )
    (net (code "43") (name "SYS_5V0") (class "Default")
      (node (ref "C4") (pin "2") (pinfunction "2_2") (pintype "input"))
      (node (ref "D1") (pin "2") (pinfunction "A_2") (pintype "unspecified"))
      (node (ref "D3") (pin "5") (pinfunction "VBUS_5") (pintype "unspecified"))
      (node (ref "U2") (pin "12") (pinfunction "V5_12") (pintype "unspecified"))
      (node (ref "U6") (pin "10") (pinfunction "10_10") (pintype "unspecified"))
      (node (ref "USB1") (pin "A4") (pinfunction "VBUS_A4") (pintype "unspecified"))
      (node (ref "USB1") (pin "A9") (pinfunction "VBUS_A9") (pintype "unspecified"))
    )
    (net (code "44") (name "unconnected-(U2-DM3-Pad3)") (class "Default")
      (node (ref "U2") (pin "3") (pinfunction "DM3_3") (pintype "unspecified+no_connect"))
    )
    (net (code "45") (name "unconnected-(U2-DM4-Pad1)") (class "Default")
      (node (ref "U2") (pin "1") (pinfunction "DM4_1") (pintype "unspecified+no_connect"))
    )
    (net (code "46") (name "unconnected-(U2-DP3-Pad4)") (class "Default")
      (node (ref "U2") (pin "4") (pinfunction "DP3_4") (pintype "unspecified+no_connect"))
    )
    (net (code "47") (name "unconnected-(U2-DP4-Pad2)") (class "Default")
      (node (ref "U2") (pin "2") (pinfunction "DP4_2") (pintype "unspecified+no_connect"))
    )
    (net (code "48") (name "unconnected-(U2-RESET#{slash}CDP-Pad9)") (class "Default")
      (node (ref "U2") (pin "9") (pinfunction "RESET#/CDP_9") (pintype "unspecified+no_connect"))
    )
    (net (code "49") (name "unconnected-(U5-NFC1{slash}P0.09-Pad11)") (class "Default")
      (node (ref "U5") (pin "11") (pinfunction "NFC1/P0.09_11") (pintype "unspecified+no_connect"))
    )
    (net (code "50") (name "unconnected-(U5-NFC2{slash}P0.10-Pad12)") (class "Default")
      (node (ref "U5") (pin "12") (pinfunction "NFC2/P0.10_12") (pintype "unspecified+no_connect"))
    )
    (net (code "51") (name "unconnected-(U5-P0.02{slash}AIN0-Pad4)") (class "Default")
      (node (ref "U5") (pin "4") (pinfunction "P0.02/AIN0_4") (pintype "unspecified+no_connect"))
    )
    (net (code "52") (name "unconnected-(U5-P0.03{slash}AIN1-Pad5)") (class "Default")
      (node (ref "U5") (pin "5") (pinfunction "P0.03/AIN1_5") (pintype "unspecified+no_connect"))
    )
    (net (code "53") (name "unconnected-(U5-P0.04{slash}AIN2-Pad6)") (class "Default")
      (node (ref "U5") (pin "6") (pinfunction "P0.04/AIN2_6") (pintype "unspecified+no_connect"))
    )
    (net (code "54") (name "unconnected-(U5-P0.05{slash}AIN3-Pad7)") (class "Default")
      (node (ref "U5") (pin "7") (pinfunction "P0.05/AIN3_7") (pintype "unspecified+no_connect"))
    )
    (net (code "55") (name "unconnected-(U5-P0.06-Pad8)") (class "Default")
      (node (ref "U5") (pin "8") (pinfunction "P0.06_8") (pintype "unspecified+no_connect"))
    )
    (net (code "56") (name "unconnected-(U5-P0.11-Pad14)") (class "Default")
      (node (ref "U5") (pin "14") (pinfunction "P0.11_14") (pintype "unspecified+no_connect"))
    )
    (net (code "57") (name "unconnected-(U5-P0.12-Pad15)") (class "Default")
      (node (ref "U5") (pin "15") (pinfunction "P0.12_15") (pintype "unspecified+no_connect"))
    )
    (net (code "58") (name "unconnected-(U5-P0.13-Pad16)") (class "Default")
      (node (ref "U5") (pin "16") (pinfunction "P0.13_16") (pintype "unspecified+no_connect"))
    )
    (net (code "59") (name "unconnected-(U5-P0.14-Pad17)") (class "Default")
      (node (ref "U5") (pin "17") (pinfunction "P0.14_17") (pintype "unspecified+no_connect"))
    )
    (net (code "60") (name "unconnected-(U5-P0.15-Pad18)") (class "Default")
      (node (ref "U5") (pin "18") (pinfunction "P0.15_18") (pintype "unspecified+no_connect"))
    )
    (net (code "61") (name "unconnected-(U5-P0.16-Pad19)") (class "Default")
      (node (ref "U5") (pin "19") (pinfunction "P0.16_19") (pintype "unspecified+no_connect"))
    )
    (net (code "62") (name "unconnected-(U5-P0.17-Pad20)") (class "Default")
      (node (ref "U5") (pin "20") (pinfunction "P0.17_20") (pintype "unspecified+no_connect"))
    )
    (net (code "63") (name "unconnected-(U5-P0.18-Pad21)") (class "Default")
      (node (ref "U5") (pin "21") (pinfunction "P0.18_21") (pintype "unspecified+no_connect"))
    )
    (net (code "64") (name "unconnected-(U5-P0.21{slash}nRESET-Pad24)") (class "Default")
      (node (ref "U5") (pin "24") (pinfunction "P0.21/nRESET_24") (pintype "unspecified+no_connect"))
    )
    (net (code "65") (name "unconnected-(U5-P0.22-Pad27)") (class "Default")
      (node (ref "U5") (pin "27") (pinfunction "P0.22_27") (pintype "unspecified+no_connect"))
    )
    (net (code "66") (name "unconnected-(U5-P0.23-Pad28)") (class "Default")
      (node (ref "U5") (pin "28") (pinfunction "P0.23_28") (pintype "unspecified+no_connect"))
    )
    (net (code "67") (name "unconnected-(U5-P0.24-Pad29)") (class "Default")
      (node (ref "U5") (pin "29") (pinfunction "P0.24_29") (pintype "unspecified+no_connect"))
    )
    (net (code "68") (name "unconnected-(U5-P0.25{slash}O32M-Pad37)") (class "Default")
      (node (ref "U5") (pin "37") (pinfunction "P0.25/O32M_37") (pintype "unspecified+no_connect"))
    )
    (net (code "69") (name "unconnected-(U5-P0.26-Pad38)") (class "Default")
      (node (ref "U5") (pin "38") (pinfunction "P0.26_38") (pintype "unspecified+no_connect"))
    )
    (net (code "70") (name "unconnected-(U5-P0.27-Pad39)") (class "Default")
      (node (ref "U5") (pin "39") (pinfunction "P0.27_39") (pintype "unspecified+no_connect"))
    )
    (net (code "71") (name "unconnected-(U5-P0.28{slash}AIN4-Pad40)") (class "Default")
      (node (ref "U5") (pin "40") (pinfunction "P0.28/AIN4_40") (pintype "unspecified+no_connect"))
    )
    (net (code "72") (name "unconnected-(U5-P0.29{slash}AIN5-Pad41)") (class "Default")
      (node (ref "U5") (pin "41") (pinfunction "P0.29/AIN5_41") (pintype "unspecified+no_connect"))
    )
    (net (code "73") (name "unconnected-(U5-P0.30{slash}AIN6-Pad42)") (class "Default")
      (node (ref "U5") (pin "42") (pinfunction "P0.30/AIN6_42") (pintype "unspecified+no_connect"))
    )
    (net (code "74") (name "unconnected-(U5-P0.31{slash}AIN7-Pad43)") (class "Default")
      (node (ref "U5") (pin "43") (pinfunction "P0.31/AIN7_43") (pintype "unspecified+no_connect"))
    )
    (net (code "75") (name "unconnected-(U7-CTS#-Pad5)") (class "Default")
      (node (ref "U7") (pin "5") (pinfunction "CTS#_5") (pintype "unspecified+no_connect"))
    )
    (net (code "76") (name "unconnected-(U7-RTS#-Pad4)") (class "Default")
      (node (ref "U7") (pin "4") (pinfunction "RTS#_4") (pintype "unspecified+no_connect"))
    )
    (net (code "77") (name "unconnected-(U7-TNOW-Pad6)") (class "Default")
      (node (ref "U7") (pin "6") (pinfunction "TNOW_6") (pintype "unspecified+no_connect"))
    )
    (net (code "78") (name "unconnected-(USB1-EP-Pad1)") (class "Default")
      (node (ref "USB1") (pin "1") (pinfunction "EP_1") (pintype "unspecified+no_connect"))
    )
    (net (code "79") (name "unconnected-(USB1-SBU1-PadA8)") (class "Default")
      (node (ref "USB1") (pin "A8") (pinfunction "SBU1_A8") (pintype "unspecified+no_connect"))
    )
    (net (code "80") (name "unconnected-(USB1-SBU2-PadB8)") (class "Default")
      (node (ref "USB1") (pin "B8") (pinfunction "SBU2_B8") (pintype "unspecified+no_connect"))
    )
  )
)
